# Main.net
KiCad netlist of a schematic drawn in Altium Designer
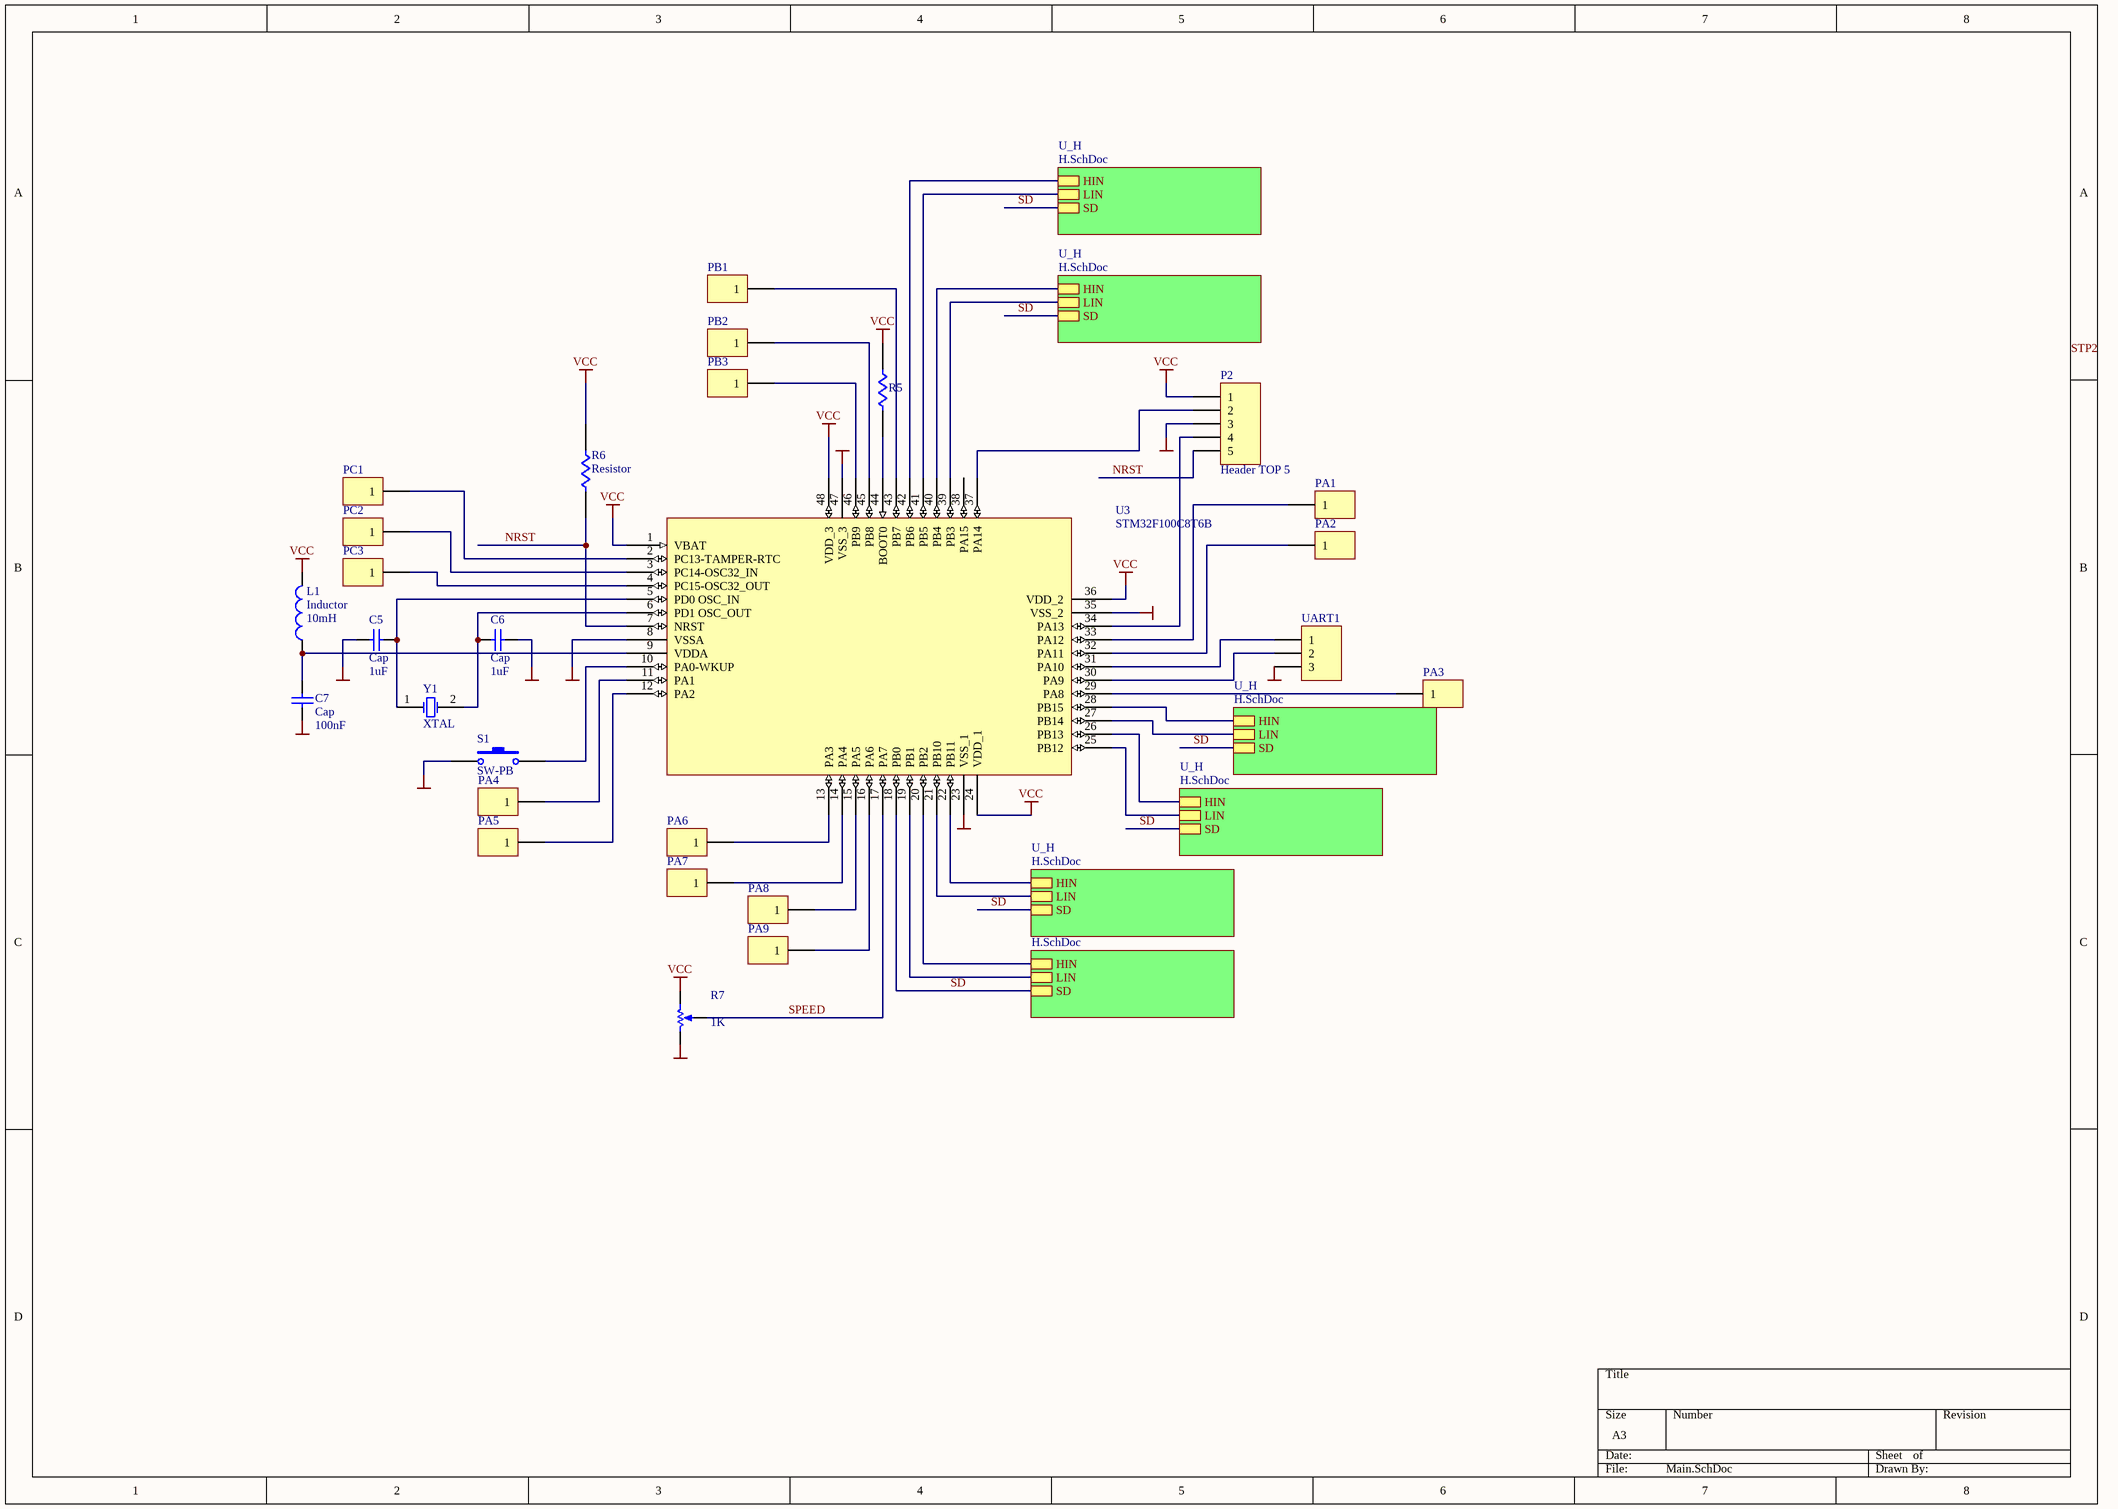
[diagram p0: Main.SchDoc]

(export (version "E")
  (design (tool "Eeschema 10.0.6"))
  (components
    (comp (ref "C5")
      (value "Cap")
      (footprint "6-0805_M")
      (description "Capacitor")
      (fields (field (name "ALTIUM_VALUE") "1uF") (field (name "PUBLISHER") "Altium Limited"))
      (libsource (lib "Project") (part "Cap"))
    )
    (comp (ref "C6")
      (value "Cap")
      (footprint "6-0805_M")
      (description "Capacitor")
      (fields (field (name "ALTIUM_VALUE") "1uF") (field (name "PUBLISHER") "Altium Limited"))
      (libsource (lib "Project") (part "Cap"))
    )
    (comp (ref "C7")
      (value "Cap")
      (footprint "6-0805_M")
      (description "Capacitor")
      (fields (field (name "ALTIUM_VALUE") "100nF") (field (name "PUBLISHER") "Altium Limited"))
      (libsource (lib "Project") (part "Cap"))
    )
    (comp (ref "L1")
      (value "Inductor")
      (footprint "INDC4532")
      (fields (field (name "ALTIUM_VALUE") "10mH") (field (name "PUBLISHER") "Altium Limited"))
      (libsource (lib "Project") (part "Inductor"))
    )
    (comp (ref "P2")
      (value "Header TOP 5")
      (footprint "PIN_TOP_SMALL_5")
      (description "Header, 1Pin")
      (fields (field (name "PUBLISHER") "Altium Limited"))
      (libsource (lib "Project") (part "Header TOP 5"))
    )
    (comp (ref "PA1")
      (value "Header TOP 1")
      (footprint "PIN1")
      (description "Header, 1Pin")
      (fields (field (name "PUBLISHER") "Altium Limited"))
      (libsource (lib "Project") (part "Header TOP 1"))
    )
    (comp (ref "PA2")
      (value "Header TOP 1")
      (footprint "PIN1")
      (description "Header, 1Pin")
      (fields (field (name "PUBLISHER") "Altium Limited"))
      (libsource (lib "Project") (part "Header TOP 1"))
    )
    (comp (ref "PA3")
      (value "Header TOP 1")
      (footprint "PIN1")
      (description "Header, 1Pin")
      (fields (field (name "PUBLISHER") "Altium Limited"))
      (libsource (lib "Project") (part "Header TOP 1"))
    )
    (comp (ref "PA4")
      (value "Header TOP 1")
      (footprint "PIN1")
      (description "Header, 1Pin")
      (fields (field (name "PUBLISHER") "Altium Limited"))
      (libsource (lib "") (part "Header TOP 1_1"))
    )
    (comp (ref "PA5")
      (value "Header TOP 1")
      (footprint "PIN1")
      (description "Header, 1Pin")
      (fields (field (name "PUBLISHER") "Altium Limited"))
      (libsource (lib "") (part "Header TOP 1_1"))
    )
    (comp (ref "PA6")
      (value "Header TOP 1")
      (footprint "PIN1")
      (description "Header, 1Pin")
      (fields (field (name "PUBLISHER") "Altium Limited"))
      (libsource (lib "") (part "Header TOP 1_1"))
    )
    (comp (ref "PA7")
      (value "Header TOP 1")
      (footprint "PIN1")
      (description "Header, 1Pin")
      (fields (field (name "PUBLISHER") "Altium Limited"))
      (libsource (lib "") (part "Header TOP 1_1"))
    )
    (comp (ref "PA8")
      (value "Header TOP 1")
      (footprint "PIN1")
      (description "Header, 1Pin")
      (fields (field (name "PUBLISHER") "Altium Limited"))
      (libsource (lib "") (part "Header TOP 1_1"))
    )
    (comp (ref "PA9")
      (value "Header TOP 1")
      (footprint "PIN1")
      (description "Header, 1Pin")
      (fields (field (name "PUBLISHER") "Altium Limited"))
      (libsource (lib "") (part "Header TOP 1_1"))
    )
    (comp (ref "PB1")
      (value "Header TOP 1")
      (footprint "PIN1")
      (description "Header, 1Pin")
      (fields (field (name "PUBLISHER") "Altium Limited"))
      (libsource (lib "") (part "Header TOP 1_1"))
    )
    (comp (ref "PB2")
      (value "Header TOP 1")
      (footprint "PIN1")
      (description "Header, 1Pin")
      (fields (field (name "PUBLISHER") "Altium Limited"))
      (libsource (lib "") (part "Header TOP 1_1"))
    )
    (comp (ref "PB3")
      (value "Header TOP 1")
      (footprint "PIN1")
      (description "Header, 1Pin")
      (fields (field (name "PUBLISHER") "Altium Limited"))
      (libsource (lib "") (part "Header TOP 1_1"))
    )
    (comp (ref "PC1")
      (value "Header TOP 1")
      (footprint "PIN1")
      (description "Header, 1Pin")
      (fields (field (name "PUBLISHER") "Altium Limited"))
      (libsource (lib "") (part "Header TOP 1_1"))
    )
    (comp (ref "PC2")
      (value "Header TOP 1")
      (footprint "PIN1")
      (description "Header, 1Pin")
      (fields (field (name "PUBLISHER") "Altium Limited"))
      (libsource (lib "") (part "Header TOP 1_1"))
    )
    (comp (ref "PC3")
      (value "Header TOP 1")
      (footprint "PIN1")
      (description "Header, 1Pin")
      (fields (field (name "PUBLISHER") "Altium Limited"))
      (libsource (lib "") (part "Header TOP 1_1"))
    )
    (comp (ref "R5")
      (value "Resistor")
      (footprint "6-0805_M")
      (fields (field (name "PUBLISHER") "Altium Limited"))
      (libsource (lib "Project") (part "Resistor"))
    )
    (comp (ref "R6")
      (value "Resistor")
      (footprint "6-0805_M")
      (fields (field (name "PUBLISHER") "Altium Limited"))
      (libsource (lib "Project") (part "Resistor"))
    )
    (comp (ref "R7")
      (value "1K")
      (footprint "VR5")
      (description "Potentiometer")
      (fields (field (name "Comment") "RPot") (field (name "PUBLISHER") "Altium Limited"))
      (libsource (lib "Miscellaneous Devices") (part "RPot"))
    )
    (comp (ref "S1")
      (value "SW-PB")
      (footprint "SPST-2")
      (description "Switch")
      (fields (field (name "PUBLISHER") "Altium Limited"))
      (libsource (lib "Miscellaneous Devices") (part "SW-PB"))
    )
    (comp (ref "U3")
      (value "STM32F100C8T6B")
      (footprint "TQFP48_L")
      (description "STM32 ARM-based 32-bit MCU with 32 Kbytes Flash, 48-pin LQFP, Industrial Temperature")
      (fields (field (name "PUBLISHER") "Altium Limited"))
      (libsource (lib "Project") (part "STM32F100C8T6B"))
    )
    (comp (ref "UART1")
      (value "Header TOP 3")
      (footprint "PIN_TOP_SMALL_3")
      (description "Header, 1Pin")
      (fields (field (name "PUBLISHER") "Altium Limited"))
      (libsource (lib "Project") (part "Header TOP 3"))
    )
    (comp (ref "Y1")
      (value "XTAL")
      (footprint "RAD-0.3")
      (description "Crystal Oscillator")
      (fields (field (name "PUBLISHER") "Altium Limited"))
      (libsource (lib "Project") (part "XTAL"))
    )
  )
  (nets
    (net (code "1") (name "/HIN") (class "Default")
      (node (ref "U3") (pin "42") (pinfunction "PB6_42") (pintype "bidirectional"))
    )
    (net (code "2") (name "/HIN_1") (class "Default")
      (node (ref "U3") (pin "20") (pinfunction "PB2_20") (pintype "bidirectional"))
    )
    (net (code "3") (name "/HIN_2") (class "Default")
      (node (ref "U3") (pin "22") (pinfunction "PB11_22") (pintype "bidirectional"))
    )
    (net (code "4") (name "/HIN_3") (class "Default")
      (node (ref "U3") (pin "26") (pinfunction "PB13_26") (pintype "bidirectional"))
    )
    (net (code "5") (name "/HIN_4") (class "Default")
      (node (ref "U3") (pin "28") (pinfunction "PB15_28") (pintype "bidirectional"))
    )
    (net (code "6") (name "/HIN_5") (class "Default")
      (node (ref "U3") (pin "40") (pinfunction "PB4_40") (pintype "bidirectional"))
    )
    (net (code "7") (name "/LIN") (class "Default")
      (node (ref "U3") (pin "41") (pinfunction "PB5_41") (pintype "bidirectional"))
    )
    (net (code "8") (name "/LIN_1") (class "Default")
      (node (ref "U3") (pin "19") (pinfunction "PB1_19") (pintype "bidirectional"))
    )
    (net (code "9") (name "/LIN_2") (class "Default")
      (node (ref "U3") (pin "21") (pinfunction "PB10_21") (pintype "bidirectional"))
    )
    (net (code "10") (name "/LIN_3") (class "Default")
      (node (ref "U3") (pin "25") (pinfunction "PB12_25") (pintype "bidirectional"))
    )
    (net (code "11") (name "/LIN_4") (class "Default")
      (node (ref "U3") (pin "27") (pinfunction "PB14_27") (pintype "bidirectional"))
    )
    (net (code "12") (name "/LIN_5") (class "Default")
      (node (ref "U3") (pin "39") (pinfunction "PB3_39") (pintype "bidirectional"))
    )
    (net (code "13") (name "/NRST") (class "Default")
      (node (ref "P2") (pin "5") (pinfunction "5_5") (pintype "passive"))
      (node (ref "R6") (pin "2") (pinfunction "2_2") (pintype "passive"))
      (node (ref "U3") (pin "7") (pinfunction "NRST_7") (pintype "bidirectional"))
    )
    (net (code "14") (name "/SD") (class "Default")
      (node (ref "U3") (pin "18") (pinfunction "PB0_18") (pintype "bidirectional"))
    )
    (net (code "15") (name "/SPEED") (class "Default")
      (node (ref "R7") (pin "3") (pinfunction "TAP_3") (pintype "passive"))
      (node (ref "U3") (pin "17") (pinfunction "PA7_17") (pintype "bidirectional"))
    )
    (net (code "17") (name "GND") (class "Default")
      (node (ref "C5") (pin "2") (pinfunction "2_2") (pintype "passive"))
      (node (ref "C6") (pin "1") (pinfunction "1_1") (pintype "passive"))
      (node (ref "C7") (pin "1") (pinfunction "1_1") (pintype "passive"))
      (node (ref "P2") (pin "3") (pinfunction "3_3") (pintype "passive"))
      (node (ref "R7") (pin "2") (pinfunction "BOT_2") (pintype "passive"))
      (node (ref "S1") (pin "1") (pinfunction "1_1") (pintype "passive"))
      (node (ref "U3") (pin "23") (pinfunction "VSS_1_23") (pintype "power_in"))
      (node (ref "U3") (pin "35") (pinfunction "VSS_2_35") (pintype "power_in"))
      (node (ref "U3") (pin "47") (pinfunction "VSS_3_47") (pintype "power_in"))
      (node (ref "U3") (pin "8") (pinfunction "VSSA_8") (pintype "power_in"))
      (node (ref "UART1") (pin "3") (pinfunction "3_3") (pintype "passive"))
    )
    (net (code "18") (name "Net-(U3-BOOT0)") (class "Default")
      (node (ref "R5") (pin "1") (pinfunction "1_1") (pintype "passive"))
      (node (ref "U3") (pin "44") (pinfunction "BOOT0_44") (pintype "input"))
    )
    (net (code "19") (name "Net-(U3-PA0-WKUP)") (class "Default")
      (node (ref "S1") (pin "2") (pinfunction "2_2") (pintype "passive"))
      (node (ref "U3") (pin "10") (pinfunction "PA0-WKUP_10") (pintype "bidirectional"))
    )
    (net (code "20") (name "Net-(U3-PA1)") (class "Default")
      (node (ref "PA4") (pin "1") (pinfunction "1_1") (pintype "passive"))
      (node (ref "U3") (pin "11") (pinfunction "PA1_11") (pintype "bidirectional"))
    )
    (net (code "21") (name "Net-(U3-PA2)") (class "Default")
      (node (ref "PA5") (pin "1") (pinfunction "1_1") (pintype "passive"))
      (node (ref "U3") (pin "12") (pinfunction "PA2_12") (pintype "bidirectional"))
    )
    (net (code "22") (name "Net-(U3-PA3)") (class "Default")
      (node (ref "PA6") (pin "1") (pinfunction "1_1") (pintype "passive"))
      (node (ref "U3") (pin "13") (pinfunction "PA3_13") (pintype "bidirectional"))
    )
    (net (code "23") (name "Net-(U3-PA4)") (class "Default")
      (node (ref "PA7") (pin "1") (pinfunction "1_1") (pintype "passive"))
      (node (ref "U3") (pin "14") (pinfunction "PA4_14") (pintype "bidirectional"))
    )
    (net (code "24") (name "Net-(U3-PA5)") (class "Default")
      (node (ref "PA8") (pin "1") (pinfunction "1_1") (pintype "passive"))
      (node (ref "U3") (pin "15") (pinfunction "PA5_15") (pintype "bidirectional"))
    )
    (net (code "25") (name "Net-(U3-PA6)") (class "Default")
      (node (ref "PA9") (pin "1") (pinfunction "1_1") (pintype "passive"))
      (node (ref "U3") (pin "16") (pinfunction "PA6_16") (pintype "bidirectional"))
    )
    (net (code "26") (name "Net-(U3-PA8)") (class "Default")
      (node (ref "PA3") (pin "1") (pinfunction "1_1") (pintype "passive"))
      (node (ref "U3") (pin "29") (pinfunction "PA8_29") (pintype "bidirectional"))
    )
    (net (code "27") (name "Net-(U3-PA9)") (class "Default")
      (node (ref "U3") (pin "30") (pinfunction "PA9_30") (pintype "bidirectional"))
      (node (ref "UART1") (pin "2") (pinfunction "2_2") (pintype "passive"))
    )
    (net (code "28") (name "Net-(U3-PA10)") (class "Default")
      (node (ref "U3") (pin "31") (pinfunction "PA10_31") (pintype "bidirectional"))
      (node (ref "UART1") (pin "1") (pinfunction "1_1") (pintype "passive"))
    )
    (net (code "29") (name "Net-(U3-PA11)") (class "Default")
      (node (ref "PA2") (pin "1") (pinfunction "1_1") (pintype "passive"))
      (node (ref "U3") (pin "32") (pinfunction "PA11_32") (pintype "bidirectional"))
    )
    (net (code "30") (name "Net-(U3-PA12)") (class "Default")
      (node (ref "PA1") (pin "1") (pinfunction "1_1") (pintype "passive"))
      (node (ref "U3") (pin "33") (pinfunction "PA12_33") (pintype "bidirectional"))
    )
    (net (code "31") (name "Net-(U3-PA13)") (class "Default")
      (node (ref "P2") (pin "4") (pinfunction "4_4") (pintype "passive"))
      (node (ref "U3") (pin "34") (pinfunction "PA13_34") (pintype "bidirectional"))
    )
    (net (code "32") (name "Net-(U3-PA14)") (class "Default")
      (node (ref "P2") (pin "2") (pinfunction "2_2") (pintype "passive"))
      (node (ref "U3") (pin "37") (pinfunction "PA14_37") (pintype "bidirectional"))
    )
    (net (code "33") (name "Net-(U3-PB7)") (class "Default")
      (node (ref "PB1") (pin "1") (pinfunction "1_1") (pintype "passive"))
      (node (ref "U3") (pin "43") (pinfunction "PB7_43") (pintype "bidirectional"))
    )
    (net (code "34") (name "Net-(U3-PB8)") (class "Default")
      (node (ref "PB2") (pin "1") (pinfunction "1_1") (pintype "passive"))
      (node (ref "U3") (pin "45") (pinfunction "PB8_45") (pintype "bidirectional"))
    )
    (net (code "35") (name "Net-(U3-PB9)") (class "Default")
      (node (ref "PB3") (pin "1") (pinfunction "1_1") (pintype "passive"))
      (node (ref "U3") (pin "46") (pinfunction "PB9_46") (pintype "bidirectional"))
    )
    (net (code "36") (name "Net-(U3-PC13-TAMPER-RTC)") (class "Default")
      (node (ref "PC1") (pin "1") (pinfunction "1_1") (pintype "passive"))
      (node (ref "U3") (pin "2") (pinfunction "PC13-TAMPER-RTC_2") (pintype "bidirectional"))
    )
    (net (code "37") (name "Net-(U3-PC14-OSC32_IN)") (class "Default")
      (node (ref "PC2") (pin "1") (pinfunction "1_1") (pintype "passive"))
      (node (ref "U3") (pin "3") (pinfunction "PC14-OSC32_IN_3") (pintype "bidirectional"))
    )
    (net (code "38") (name "Net-(U3-PC15-OSC32_OUT)") (class "Default")
      (node (ref "PC3") (pin "1") (pinfunction "1_1") (pintype "passive"))
      (node (ref "U3") (pin "4") (pinfunction "PC15-OSC32_OUT_4") (pintype "bidirectional"))
    )
    (net (code "39") (name "Net-(U3-PD0_OSC_IN)") (class "Default")
      (node (ref "C5") (pin "1") (pinfunction "1_1") (pintype "passive"))
      (node (ref "U3") (pin "5") (pinfunction "PD0_OSC_IN_5") (pintype "bidirectional"))
      (node (ref "Y1") (pin "1") (pinfunction "OSC1_1") (pintype "passive"))
    )
    (net (code "40") (name "Net-(U3-PD1_OSC_OUT)") (class "Default")
      (node (ref "C6") (pin "2") (pinfunction "2_2") (pintype "passive"))
      (node (ref "U3") (pin "6") (pinfunction "PD1_OSC_OUT_6") (pintype "bidirectional"))
      (node (ref "Y1") (pin "2") (pinfunction "OSC2_2") (pintype "passive"))
    )
    (net (code "41") (name "Net-(U3-VDDA)") (class "Default")
      (node (ref "C7") (pin "2") (pinfunction "2_2") (pintype "passive"))
      (node (ref "L1") (pin "1") (pinfunction "1_1") (pintype "passive"))
      (node (ref "U3") (pin "9") (pinfunction "VDDA_9") (pintype "power_in"))
    )
    (net (code "42") (name "VCC") (class "Default")
      (node (ref "L1") (pin "2") (pinfunction "2_2") (pintype "passive"))
      (node (ref "P2") (pin "1") (pinfunction "1_1") (pintype "passive"))
      (node (ref "R5") (pin "2") (pinfunction "2_2") (pintype "passive"))
      (node (ref "R6") (pin "1") (pinfunction "1_1") (pintype "passive"))
      (node (ref "R7") (pin "1") (pinfunction "TOP_1") (pintype "passive"))
      (node (ref "U3") (pin "1") (pinfunction "VBAT_1") (pintype "input"))
      (node (ref "U3") (pin "24") (pinfunction "VDD_1_24") (pintype "power_in"))
      (node (ref "U3") (pin "36") (pinfunction "VDD_2_36") (pintype "power_in"))
      (node (ref "U3") (pin "48") (pinfunction "VDD_3_48") (pintype "bidirectional"))
    )
    (net (code "43") (name "unconnected-(U3-PA15-Pad38)") (class "Default")
      (node (ref "U3") (pin "38") (pinfunction "PA15_38") (pintype "bidirectional"))
    )
  )
)
